# RTC_and_EEPROM.net
KiCad netlist of a schematic drawn in Altium Designer
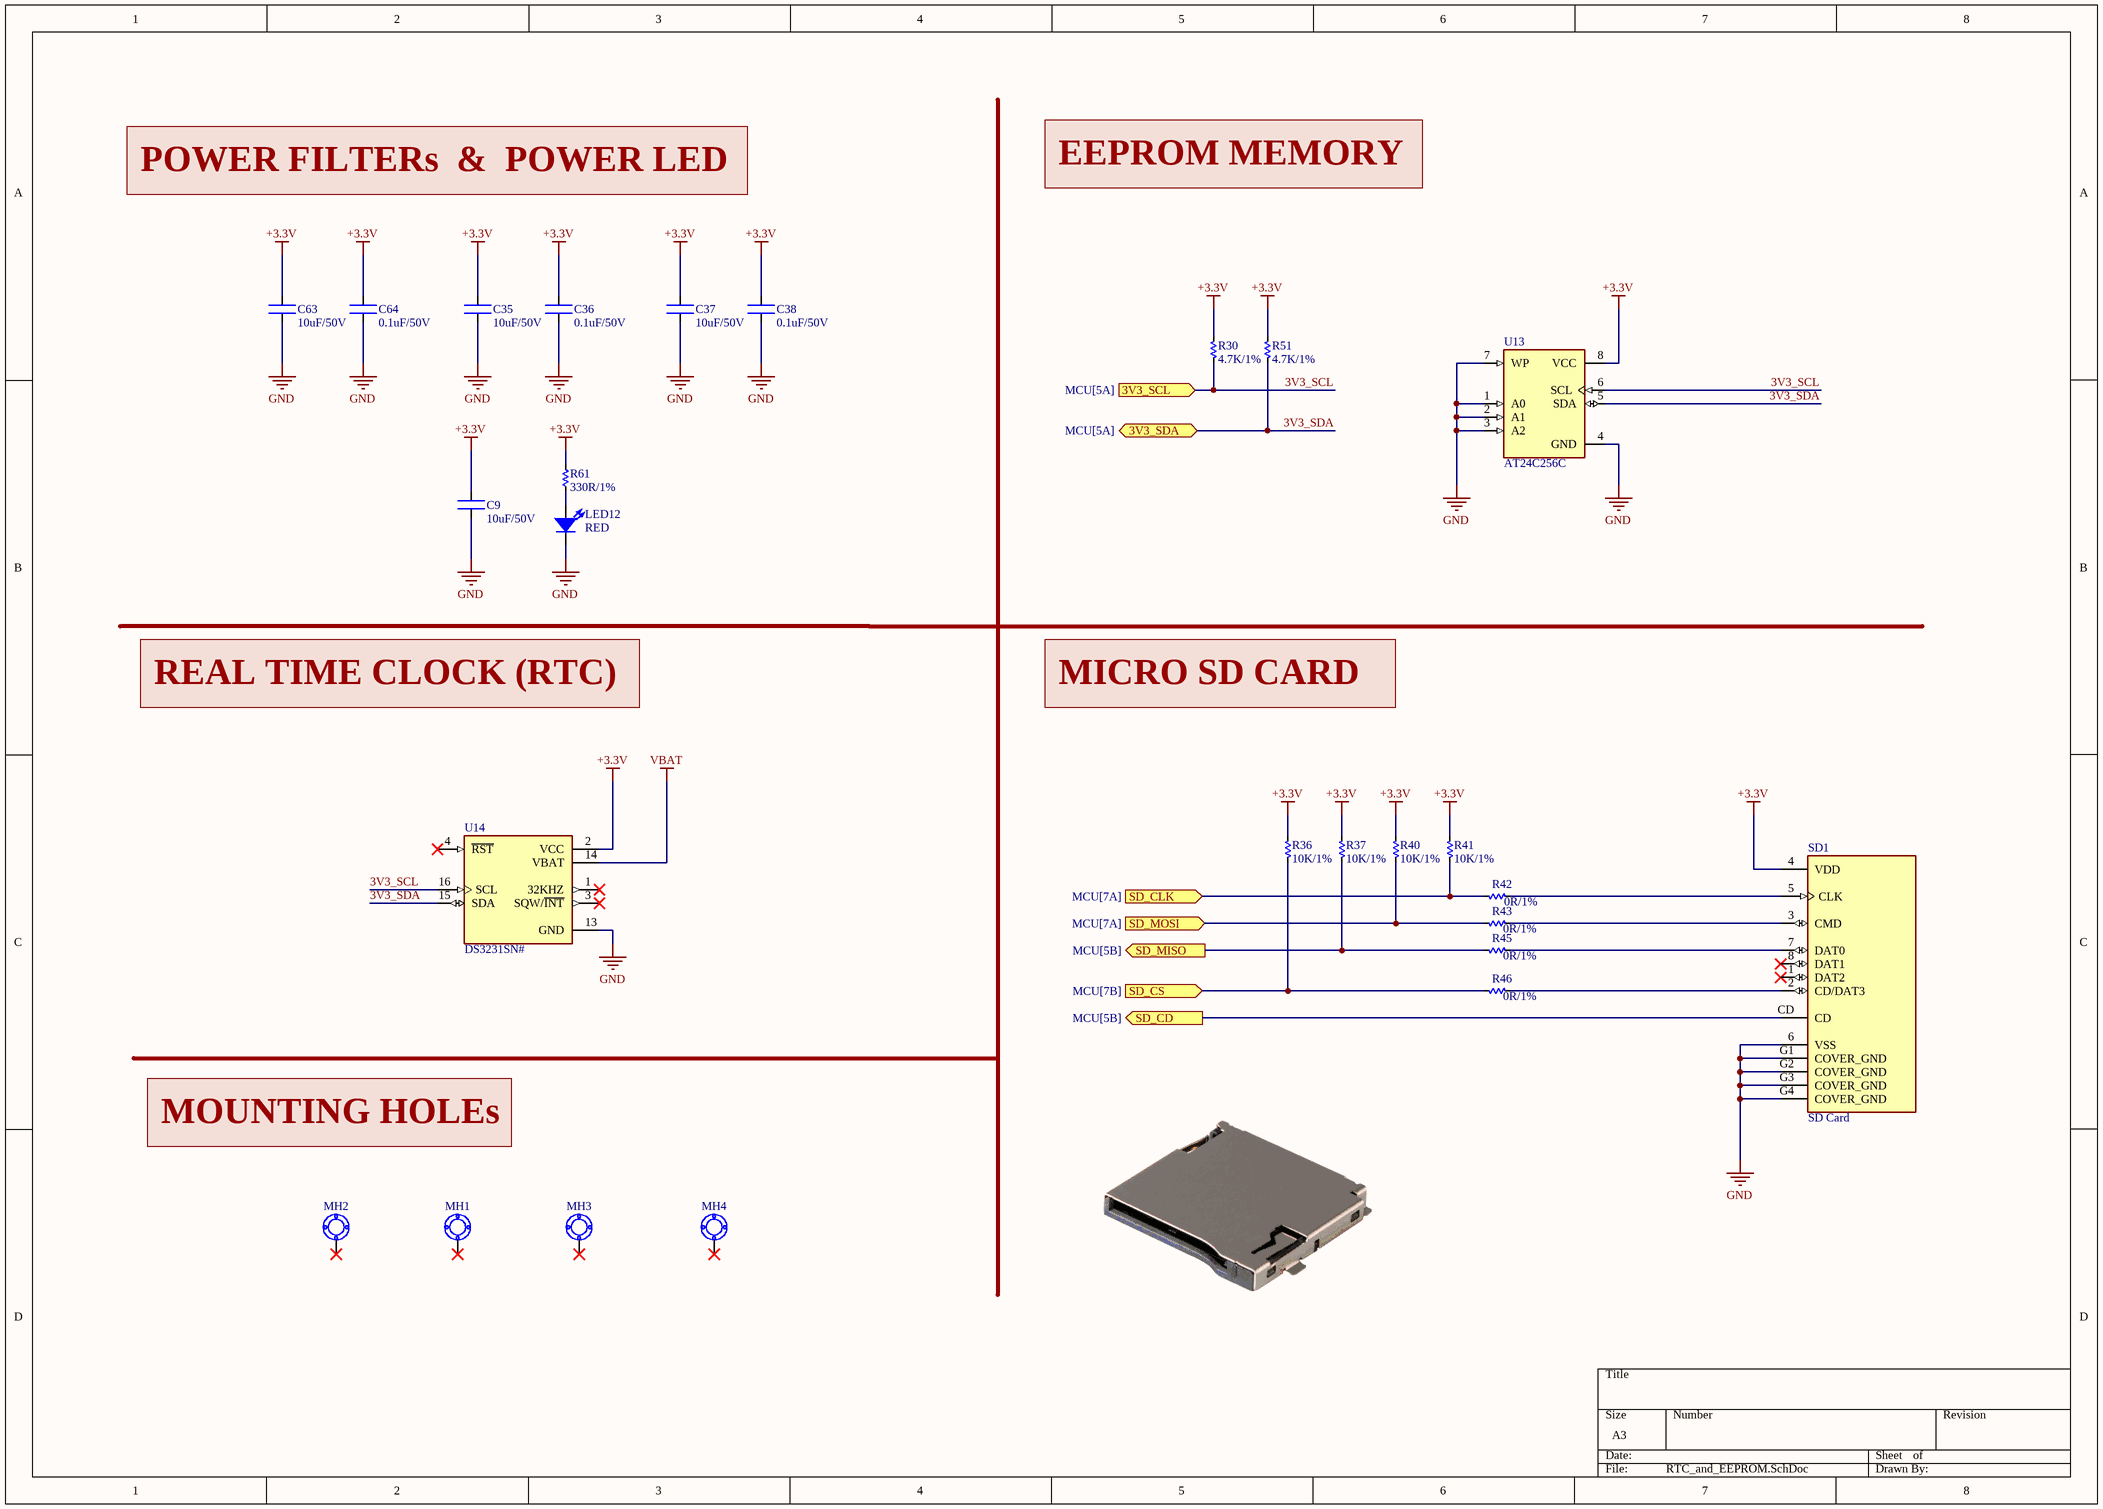
[diagram p0: RTC_and_EEPROM.SchDoc]

(export (version "E")
  (design (tool "Eeschema 10.0.6"))
  (components
    (comp (ref "C9")
      (value "10uF/50V")
      (footprint "CAP - 0603")
      (description "CAPACITOR SMD - KEMET")
      (libsource (lib "NewLibrary") (part "CAPACITOR"))
    )
    (comp (ref "C35")
      (value "10uF/50V")
      (footprint "CAP - 0603")
      (description "CAPACITOR SMD - KEMET")
      (libsource (lib "NewLibrary") (part "CAPACITOR"))
    )
    (comp (ref "C36")
      (value "0.1uF/50V")
      (footprint "CAP - 0603")
      (description "CAPACITOR SMD - KEMET")
      (libsource (lib "NewLibrary") (part "CAPACITOR"))
    )
    (comp (ref "C37")
      (value "10uF/50V")
      (footprint "CAP - 0603")
      (description "CAPACITOR SMD - KEMET")
      (libsource (lib "NewLibrary") (part "CAPACITOR"))
    )
    (comp (ref "C38")
      (value "0.1uF/50V")
      (footprint "CAP - 0603")
      (description "CAPACITOR SMD - KEMET")
      (libsource (lib "NewLibrary") (part "CAPACITOR"))
    )
    (comp (ref "C63")
      (value "10uF/50V")
      (footprint "CAP - 0603")
      (description "CAPACITOR SMD - KEMET")
      (libsource (lib "NewLibrary") (part "CAPACITOR"))
    )
    (comp (ref "C64")
      (value "0.1uF/50V")
      (footprint "CAP - 0603")
      (description "CAPACITOR SMD - KEMET")
      (libsource (lib "NewLibrary") (part "CAPACITOR"))
    )
    (comp (ref "LED12")
      (value "RED")
      (footprint "RED_LED_0603")
      (description "LED SMD")
      (libsource (lib "NewLibrary") (part "LED_SMD"))
    )
    (comp (ref "MH1")
      (value "MOUNTING HOLE")
      (footprint "Mounting hole_2")
      (description "Mounting hole")
      (libsource (lib "NewLibrary") (part "MOUNTING HOLE"))
    )
    (comp (ref "MH2")
      (value "MOUNTING HOLE")
      (footprint "Mounting hole_2")
      (description "Mounting hole")
      (libsource (lib "NewLibrary") (part "MOUNTING HOLE"))
    )
    (comp (ref "MH3")
      (value "MOUNTING HOLE")
      (footprint "Mounting hole_2")
      (description "Mounting hole")
      (libsource (lib "NewLibrary") (part "MOUNTING HOLE"))
    )
    (comp (ref "MH4")
      (value "MOUNTING HOLE")
      (footprint "Mounting hole_2")
      (description "Mounting hole")
      (libsource (lib "NewLibrary") (part "MOUNTING HOLE"))
    )
    (comp (ref "R30")
      (value "4.7K/1%")
      (footprint "RES - 0603")
      (description "Resistor SMD - YAGEO")
      (libsource (lib "NewLibrary") (part "RESISTOR"))
    )
    (comp (ref "R36")
      (value "10K/1%")
      (footprint "RES - 0603")
      (description "Resistor SMD - YAGEO")
      (libsource (lib "NewLibrary") (part "RESISTOR"))
    )
    (comp (ref "R37")
      (value "10K/1%")
      (footprint "RES - 0603")
      (description "Resistor SMD - YAGEO")
      (libsource (lib "NewLibrary") (part "RESISTOR"))
    )
    (comp (ref "R40")
      (value "10K/1%")
      (footprint "RES - 0603")
      (description "Resistor SMD - YAGEO")
      (libsource (lib "NewLibrary") (part "RESISTOR"))
    )
    (comp (ref "R41")
      (value "10K/1%")
      (footprint "RES - 0603")
      (description "Resistor SMD - YAGEO")
      (libsource (lib "NewLibrary") (part "RESISTOR"))
    )
    (comp (ref "R42")
      (value "0R/1%")
      (footprint "RES - 0603")
      (description "Resistor SMD - YAGEO")
      (libsource (lib "NewLibrary") (part "RESISTOR"))
    )
    (comp (ref "R43")
      (value "0R/1%")
      (footprint "RES - 0603")
      (description "Resistor SMD - YAGEO")
      (libsource (lib "NewLibrary") (part "RESISTOR"))
    )
    (comp (ref "R45")
      (value "0R/1%")
      (footprint "RES - 0603")
      (description "Resistor SMD - YAGEO")
      (libsource (lib "NewLibrary") (part "RESISTOR"))
    )
    (comp (ref "R46")
      (value "0R/1%")
      (footprint "RES - 0603")
      (description "Resistor SMD - YAGEO")
      (libsource (lib "NewLibrary") (part "RESISTOR"))
    )
    (comp (ref "R51")
      (value "4.7K/1%")
      (footprint "RES - 0603")
      (description "Resistor SMD - YAGEO")
      (libsource (lib "NewLibrary") (part "RESISTOR"))
    )
    (comp (ref "R61")
      (value "330R/1%")
      (footprint "RES - 0603")
      (description "Resistor SMD - YAGEO")
      (libsource (lib "NewLibrary") (part "RESISTOR"))
    )
    (comp (ref "SD1")
      (value "SD Card")
      (footprint "MICRO SD CARD")
      (libsource (lib "NewLibrary") (part "SD Card"))
    )
    (comp (ref "U13")
      (value "AT24C256C")
      (footprint "SOIC-8")
      (description "EEPROM Memory IC 256Kb (32K x 8), I2C Protocol")
      (libsource (lib "NewLibrary") (part "AT24C256C"))
    )
    (comp (ref "U14")
      (value "DS3231SN#")
      (footprint "SOIC -16")
      (description "Extremely Accurate I²C-Integrated RTC/TCXO/Crystal")
      (libsource (lib "NewLibrary") (part "DS3231SN#"))
    )
  )
  (nets
    (net (code "1") (name "+3.3V") (class "Default")
      (node (ref "C35") (pin "2") (pinfunction "2_2") (pintype "passive"))
      (node (ref "C36") (pin "2") (pinfunction "2_2") (pintype "passive"))
      (node (ref "C37") (pin "2") (pinfunction "2_2") (pintype "passive"))
      (node (ref "C38") (pin "2") (pinfunction "2_2") (pintype "passive"))
      (node (ref "C63") (pin "2") (pinfunction "2_2") (pintype "passive"))
      (node (ref "C64") (pin "2") (pinfunction "2_2") (pintype "passive"))
      (node (ref "C9") (pin "2") (pinfunction "2_2") (pintype "passive"))
      (node (ref "R30") (pin "2") (pinfunction "2_2") (pintype "passive"))
      (node (ref "R36") (pin "1") (pinfunction "1_1") (pintype "passive"))
      (node (ref "R37") (pin "1") (pinfunction "1_1") (pintype "passive"))
      (node (ref "R40") (pin "1") (pinfunction "1_1") (pintype "passive"))
      (node (ref "R41") (pin "1") (pinfunction "1_1") (pintype "passive"))
      (node (ref "R51") (pin "2") (pinfunction "2_2") (pintype "passive"))
      (node (ref "R61") (pin "1") (pinfunction "1_1") (pintype "passive"))
      (node (ref "SD1") (pin "4") (pinfunction "VDD_4") (pintype "power_in"))
      (node (ref "U13") (pin "8") (pinfunction "VCC_8") (pintype "power_in"))
      (node (ref "U14") (pin "2") (pinfunction "VCC_2") (pintype "power_in"))
    )
    (net (code "2") (name "/3V3_SCL") (class "Default")
      (node (ref "R30") (pin "1") (pinfunction "1_1") (pintype "passive"))
      (node (ref "U13") (pin "6") (pinfunction "SCL_6") (pintype "input"))
      (node (ref "U14") (pin "16") (pinfunction "SCL_16") (pintype "input"))
    )
    (net (code "3") (name "/3V3_SDA") (class "Default")
      (node (ref "R51") (pin "1") (pinfunction "1_1") (pintype "passive"))
      (node (ref "U13") (pin "5") (pinfunction "SDA_5") (pintype "bidirectional"))
      (node (ref "U14") (pin "15") (pinfunction "SDA_15") (pintype "bidirectional"))
    )
    (net (code "4") (name "/SD_CD") (class "Default")
      (node (ref "SD1") (pin "CD") (pinfunction "CD_CD") (pintype "passive"))
    )
    (net (code "5") (name "/SD_CLK") (class "Default")
      (node (ref "R41") (pin "2") (pinfunction "2_2") (pintype "passive"))
      (node (ref "R42") (pin "2") (pinfunction "2_2") (pintype "passive"))
    )
    (net (code "6") (name "/SD_CS") (class "Default")
      (node (ref "R36") (pin "2") (pinfunction "2_2") (pintype "passive"))
      (node (ref "R46") (pin "2") (pinfunction "2_2") (pintype "passive"))
    )
    (net (code "7") (name "/SD_MISO") (class "Default")
      (node (ref "R37") (pin "2") (pinfunction "2_2") (pintype "passive"))
      (node (ref "R45") (pin "2") (pinfunction "2_2") (pintype "passive"))
    )
    (net (code "8") (name "/SD_MOSI") (class "Default")
      (node (ref "R40") (pin "2") (pinfunction "2_2") (pintype "passive"))
      (node (ref "R43") (pin "2") (pinfunction "2_2") (pintype "passive"))
    )
    (net (code "9") (name "GND") (class "Default")
      (node (ref "C35") (pin "1") (pinfunction "1_1") (pintype "passive"))
      (node (ref "C36") (pin "1") (pinfunction "1_1") (pintype "passive"))
      (node (ref "C37") (pin "1") (pinfunction "1_1") (pintype "passive"))
      (node (ref "C38") (pin "1") (pinfunction "1_1") (pintype "passive"))
      (node (ref "C63") (pin "1") (pinfunction "1_1") (pintype "passive"))
      (node (ref "C64") (pin "1") (pinfunction "1_1") (pintype "passive"))
      (node (ref "C9") (pin "1") (pinfunction "1_1") (pintype "passive"))
      (node (ref "LED12") (pin "2") (pinfunction "2_2") (pintype "passive"))
      (node (ref "SD1") (pin "6") (pinfunction "VSS_6") (pintype "power_in"))
      (node (ref "SD1") (pin "G1") (pinfunction "COVER_GND_G1") (pintype "power_in"))
      (node (ref "SD1") (pin "G2") (pinfunction "COVER_GND_G2") (pintype "power_in"))
      (node (ref "SD1") (pin "G3") (pinfunction "COVER_GND_G3") (pintype "power_in"))
      (node (ref "SD1") (pin "G4") (pinfunction "COVER_GND_G4") (pintype "power_in"))
      (node (ref "U13") (pin "1") (pinfunction "A0_1") (pintype "input"))
      (node (ref "U13") (pin "2") (pinfunction "A1_2") (pintype "input"))
      (node (ref "U13") (pin "3") (pinfunction "A2_3") (pintype "input"))
      (node (ref "U13") (pin "4") (pinfunction "GND_4") (pintype "power_in"))
      (node (ref "U13") (pin "7") (pinfunction "WP_7") (pintype "input"))
      (node (ref "U14") (pin "13") (pinfunction "GND_13") (pintype "power_in"))
    )
    (net (code "10") (name "Net-(LED12-Pad1)") (class "Default")
      (node (ref "LED12") (pin "1") (pinfunction "1_1") (pintype "passive"))
      (node (ref "R61") (pin "2") (pinfunction "2_2") (pintype "passive"))
    )
    (net (code "11") (name "Net-(SD1-CD{slash}DAT3)") (class "Default")
      (node (ref "R46") (pin "1") (pinfunction "1_1") (pintype "passive"))
      (node (ref "SD1") (pin "2") (pinfunction "CD/DAT3_2") (pintype "bidirectional"))
    )
    (net (code "12") (name "Net-(SD1-CLK)") (class "Default")
      (node (ref "R42") (pin "1") (pinfunction "1_1") (pintype "passive"))
      (node (ref "SD1") (pin "5") (pinfunction "CLK_5") (pintype "input"))
    )
    (net (code "13") (name "Net-(SD1-CMD)") (class "Default")
      (node (ref "R43") (pin "1") (pinfunction "1_1") (pintype "passive"))
      (node (ref "SD1") (pin "3") (pinfunction "CMD_3") (pintype "bidirectional"))
    )
    (net (code "14") (name "Net-(SD1-DAT0)") (class "Default")
      (node (ref "R45") (pin "1") (pinfunction "1_1") (pintype "passive"))
      (node (ref "SD1") (pin "7") (pinfunction "DAT0_7") (pintype "bidirectional"))
    )
    (net (code "15") (name "VBAT") (class "Default")
      (node (ref "U14") (pin "14") (pinfunction "VBAT_14") (pintype "power_in"))
    )
    (net (code "16") (name "unconnected-(MH1-76-Pad1)") (class "Default")
      (node (ref "MH1") (pin "1") (pinfunction "76_1") (pintype "passive+no_connect"))
    )
    (net (code "17") (name "unconnected-(MH2-76-Pad1)") (class "Default")
      (node (ref "MH2") (pin "1") (pinfunction "76_1") (pintype "passive+no_connect"))
    )
    (net (code "18") (name "unconnected-(MH3-76-Pad1)") (class "Default")
      (node (ref "MH3") (pin "1") (pinfunction "76_1") (pintype "passive+no_connect"))
    )
    (net (code "19") (name "unconnected-(MH4-76-Pad1)") (class "Default")
      (node (ref "MH4") (pin "1") (pinfunction "76_1") (pintype "passive+no_connect"))
    )
    (net (code "20") (name "unconnected-(SD1-DAT1-Pad8)") (class "Default")
      (node (ref "SD1") (pin "8") (pinfunction "DAT1_8") (pintype "bidirectional+no_connect"))
    )
    (net (code "21") (name "unconnected-(SD1-DAT2-Pad1)") (class "Default")
      (node (ref "SD1") (pin "1") (pinfunction "DAT2_1") (pintype "bidirectional+no_connect"))
    )
    (net (code "22") (name "unconnected-(U14-32KHZ-Pad1)") (class "Default")
      (node (ref "U14") (pin "1") (pinfunction "32KHZ_1") (pintype "output+no_connect"))
    )
    (net (code "23") (name "unconnected-(U14-SQW{slash}~{INT}-Pad3)") (class "Default")
      (node (ref "U14") (pin "3") (pinfunction "SQW/~{INT}_3") (pintype "output+no_connect"))
    )
    (net (code "24") (name "unconnected-(U14-~{RST}-Pad4)") (class "Default")
      (node (ref "U14") (pin "4") (pinfunction "~{RST}_4") (pintype "input+no_connect"))
    )
  )
)
